# SchematicComplet.net
KiCad netlist of a schematic drawn in Altium Designer
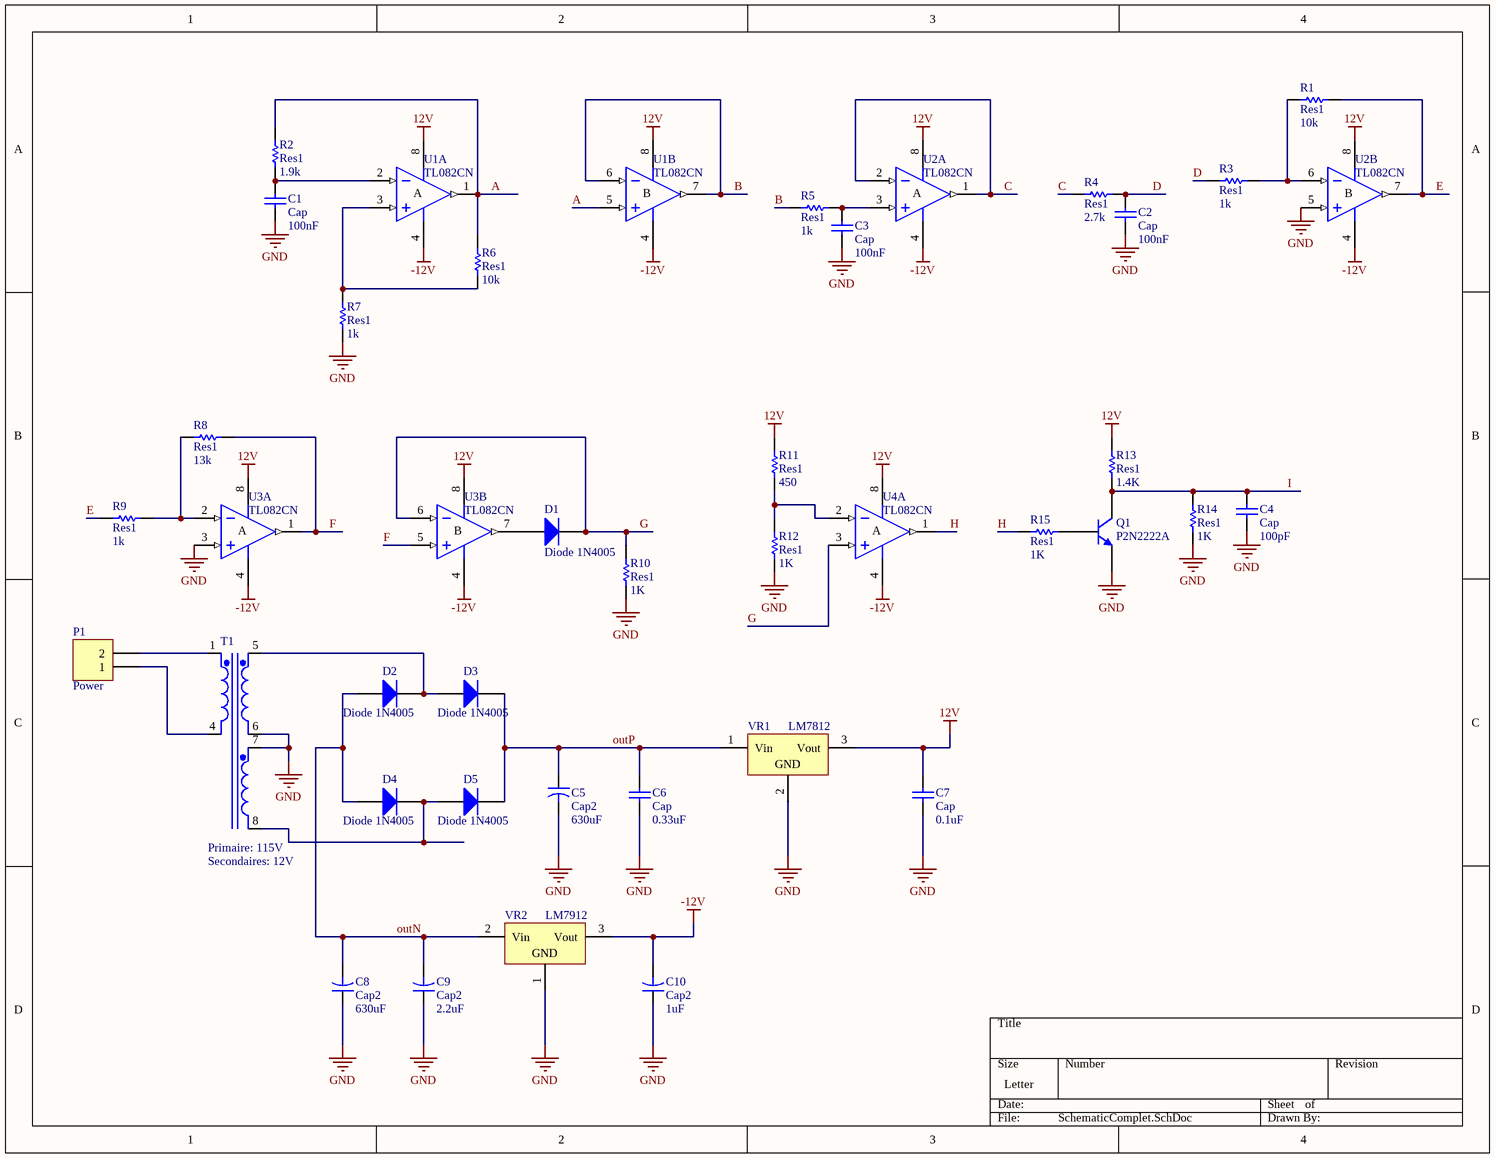
[diagram p0: SchematicComplet.SchDoc]

(export (version "E")
  (design (tool "Eeschema 10.0.6"))
  (components
    (comp (ref "C1")
      (value "Cap")
      (footprint "RAD-0.2")
      (description "Capacitor")
      (fields (field (name "ALTIUM_VALUE") "100nF") (field (name "PUBLISHER") "Altium Limited"))
      (libsource (lib "Miscellaneous Devices") (part "Cap"))
    )
    (comp (ref "C2")
      (value "Cap")
      (footprint "RAD-0.2")
      (description "Capacitor")
      (fields (field (name "ALTIUM_VALUE") "100nF") (field (name "PUBLISHER") "Altium Limited"))
      (libsource (lib "Miscellaneous Devices") (part "Cap"))
    )
    (comp (ref "C3")
      (value "Cap")
      (footprint "RAD-0.2")
      (description "Capacitor")
      (fields (field (name "ALTIUM_VALUE") "100nF") (field (name "PUBLISHER") "Altium Limited"))
      (libsource (lib "Miscellaneous Devices") (part "Cap"))
    )
    (comp (ref "C4")
      (value "Cap")
      (footprint "RAD-0.2")
      (description "Capacitor")
      (fields (field (name "ALTIUM_VALUE") "100pF") (field (name "PUBLISHER") "Altium Limited"))
      (libsource (lib "Miscellaneous Devices") (part "Cap"))
    )
    (comp (ref "C5")
      (value "Cap2")
      (footprint "Cap-10uF")
      (description "Capacitor")
      (fields (field (name "ALTIUM_VALUE") "630uF") (field (name "PUBLISHER") "Altium Limited"))
      (libsource (lib "Miscellaneous Devices") (part "Cap2"))
    )
    (comp (ref "C6")
      (value "Cap")
      (footprint "RAD-0.2")
      (description "Capacitor")
      (fields (field (name "ALTIUM_VALUE") "0.33uF") (field (name "PUBLISHER") "Altium Limited"))
      (libsource (lib "Miscellaneous Devices") (part "Cap"))
    )
    (comp (ref "C7")
      (value "Cap")
      (footprint "RAD-0.2")
      (description "Capacitor")
      (fields (field (name "ALTIUM_VALUE") "0.1uF") (field (name "PUBLISHER") "Altium Limited"))
      (libsource (lib "Miscellaneous Devices") (part "Cap"))
    )
    (comp (ref "C8")
      (value "Cap2")
      (footprint "Cap-10uF")
      (description "Capacitor")
      (fields (field (name "ALTIUM_VALUE") "630uF") (field (name "PUBLISHER") "Altium Limited"))
      (libsource (lib "Miscellaneous Devices") (part "Cap2"))
    )
    (comp (ref "C9")
      (value "Cap2")
      (footprint "Cap-10uF")
      (description "Capacitor")
      (fields (field (name "ALTIUM_VALUE") "2.2uF") (field (name "PUBLISHER") "Altium Limited"))
      (libsource (lib "Miscellaneous Devices") (part "Cap2"))
    )
    (comp (ref "C10")
      (value "Cap2")
      (footprint "Cap-10uF")
      (description "Capacitor")
      (fields (field (name "ALTIUM_VALUE") "1uF") (field (name "PUBLISHER") "Altium Limited"))
      (libsource (lib "Miscellaneous Devices") (part "Cap2"))
    )
    (comp (ref "D1")
      (value "Diode 1N4005")
      (footprint "DO-41 modifie")
      (description "1 Amp General Purpose Rectifier")
      (fields (field (name "PUBLISHER") "Altium Limited"))
      (libsource (lib "Miscellaneous Devices") (part "Diode 1N4005"))
    )
    (comp (ref "D2")
      (value "Diode 1N4005")
      (footprint "DO-41 modifie")
      (description "1 Amp General Purpose Rectifier")
      (fields (field (name "PUBLISHER") "Altium Limited"))
      (libsource (lib "Miscellaneous Devices") (part "Diode 1N4005"))
    )
    (comp (ref "D3")
      (value "Diode 1N4005")
      (footprint "DO-41 modifie")
      (description "1 Amp General Purpose Rectifier")
      (fields (field (name "PUBLISHER") "Altium Limited"))
      (libsource (lib "Miscellaneous Devices") (part "Diode 1N4005"))
    )
    (comp (ref "D4")
      (value "Diode 1N4005")
      (footprint "DO-41 modifie")
      (description "1 Amp General Purpose Rectifier")
      (fields (field (name "PUBLISHER") "Altium Limited"))
      (libsource (lib "Miscellaneous Devices") (part "Diode 1N4005"))
    )
    (comp (ref "D5")
      (value "Diode 1N4005")
      (footprint "DO-41 modifie")
      (description "1 Amp General Purpose Rectifier")
      (fields (field (name "PUBLISHER") "Altium Limited"))
      (libsource (lib "Miscellaneous Devices") (part "Diode 1N4005"))
    )
    (comp (ref "P1")
      (value "Power")
      (footprint "Bornier")
      (description "Header, 2-Pin")
      (fields (field (name "PUBLISHER") "Altium Limited"))
      (libsource (lib "Miscellaneous Connectors") (part "Header 2"))
    )
    (comp (ref "Q1")
      (value "P2N2222A")
      (footprint "29-04 modifie")
      (description "Amplifier Transistor NPN Silicon")
      (fields (field (name "PUBLISHER") "Altium Limited"))
      (libsource (lib "Motorola Discrete BJT") (part "P2N2222A"))
    )
    (comp (ref "R1")
      (value "Res1")
      (footprint "AXIAL-0.3 modifie")
      (description "Resistor")
      (fields (field (name "ALTIUM_VALUE") "10k") (field (name "PUBLISHER") "Altium Limited"))
      (libsource (lib "Miscellaneous Devices") (part "Res1"))
    )
    (comp (ref "R2")
      (value "Res1")
      (footprint "AXIAL-0.3 modifie")
      (description "Resistor")
      (fields (field (name "ALTIUM_VALUE") "1.9k") (field (name "PUBLISHER") "Altium Limited"))
      (libsource (lib "Miscellaneous Devices") (part "Res1"))
    )
    (comp (ref "R3")
      (value "Res1")
      (footprint "AXIAL-0.3 modifie")
      (description "Resistor")
      (fields (field (name "ALTIUM_VALUE") "1k") (field (name "PUBLISHER") "Altium Limited"))
      (libsource (lib "Miscellaneous Devices") (part "Res1"))
    )
    (comp (ref "R4")
      (value "Res1")
      (footprint "AXIAL-0.3 modifie")
      (description "Resistor")
      (fields (field (name "ALTIUM_VALUE") "2.7k") (field (name "PUBLISHER") "Altium Limited"))
      (libsource (lib "Miscellaneous Devices") (part "Res1"))
    )
    (comp (ref "R5")
      (value "Res1")
      (footprint "AXIAL-0.3 modifie")
      (description "Resistor")
      (fields (field (name "ALTIUM_VALUE") "1k") (field (name "PUBLISHER") "Altium Limited"))
      (libsource (lib "Miscellaneous Devices") (part "Res1"))
    )
    (comp (ref "R6")
      (value "Res1")
      (footprint "AXIAL-0.3 modifie")
      (description "Resistor")
      (fields (field (name "ALTIUM_VALUE") "10k") (field (name "PUBLISHER") "Altium Limited"))
      (libsource (lib "Miscellaneous Devices") (part "Res1"))
    )
    (comp (ref "R7")
      (value "Res1")
      (footprint "AXIAL-0.3 modifie")
      (description "Resistor")
      (fields (field (name "ALTIUM_VALUE") "1k") (field (name "PUBLISHER") "Altium Limited"))
      (libsource (lib "Miscellaneous Devices") (part "Res1"))
    )
    (comp (ref "R8")
      (value "Res1")
      (footprint "AXIAL-0.3 modifie")
      (description "Resistor")
      (fields (field (name "ALTIUM_VALUE") "13k") (field (name "PUBLISHER") "Altium Limited"))
      (libsource (lib "Miscellaneous Devices") (part "Res1"))
    )
    (comp (ref "R9")
      (value "Res1")
      (footprint "AXIAL-0.3 modifie")
      (description "Resistor")
      (fields (field (name "ALTIUM_VALUE") "1k") (field (name "PUBLISHER") "Altium Limited"))
      (libsource (lib "Miscellaneous Devices") (part "Res1"))
    )
    (comp (ref "R10")
      (value "Res1")
      (footprint "AXIAL-0.3 modifie")
      (description "Resistor")
      (fields (field (name "ALTIUM_VALUE") "1K") (field (name "PUBLISHER") "Altium Limited"))
      (libsource (lib "Miscellaneous Devices") (part "Res1"))
    )
    (comp (ref "R11")
      (value "Res1")
      (footprint "AXIAL-0.3 modifie")
      (description "Resistor")
      (fields (field (name "ALTIUM_VALUE") "450") (field (name "PUBLISHER") "Altium Limited"))
      (libsource (lib "Miscellaneous Devices") (part "Res1"))
    )
    (comp (ref "R12")
      (value "Res1")
      (footprint "AXIAL-0.3 modifie")
      (description "Resistor")
      (fields (field (name "ALTIUM_VALUE") "1K") (field (name "PUBLISHER") "Altium Limited"))
      (libsource (lib "Miscellaneous Devices") (part "Res1"))
    )
    (comp (ref "R13")
      (value "Res1")
      (footprint "AXIAL-0.3 modifie")
      (description "Resistor")
      (fields (field (name "ALTIUM_VALUE") "1.4K") (field (name "PUBLISHER") "Altium Limited"))
      (libsource (lib "Miscellaneous Devices") (part "Res1"))
    )
    (comp (ref "R14")
      (value "Res1")
      (footprint "AXIAL-0.3 modifie")
      (description "Resistor")
      (fields (field (name "ALTIUM_VALUE") "1K") (field (name "PUBLISHER") "Altium Limited"))
      (libsource (lib "Miscellaneous Devices") (part "Res1"))
    )
    (comp (ref "R15")
      (value "Res1")
      (footprint "AXIAL-0.3 modifie")
      (description "Resistor")
      (fields (field (name "ALTIUM_VALUE") "1K") (field (name "PUBLISHER") "Altium Limited"))
      (libsource (lib "Miscellaneous Devices") (part "Res1"))
    )
    (comp (ref "T1")
      (value "Trans3")
      (footprint "Transf-ST-4-24")
      (description "Three-winding Transformer (Non-Ideal)")
      (fields
        (field (name "PRIMAIRE") "115V")
        (field (name "SECONDAIRES") "12V")
        (field (name "PUBLISHER") "Altium Limited")
      )
      (libsource (lib "Miscellaneous Devices") (part "Trans3"))
    )
    (comp (ref "U1")
      (value "TL082CN")
      (footprint "TL082CN")
      (description "General-Purpose J-FET Dual Operational Amplifier")
      (fields (field (name "PUBLISHER") "Altium Limited"))
      (libsource (lib "ST Operational Amplifier") (part "TL082CN"))
    )
    (comp (ref "U2")
      (value "TL082CN")
      (footprint "TL082CN")
      (description "General-Purpose J-FET Dual Operational Amplifier")
      (fields (field (name "PUBLISHER") "Altium Limited"))
      (libsource (lib "ST Operational Amplifier") (part "TL082CN"))
    )
    (comp (ref "U3")
      (value "TL082CN")
      (footprint "TL082CN")
      (description "General-Purpose J-FET Dual Operational Amplifier")
      (fields (field (name "PUBLISHER") "Altium Limited"))
      (libsource (lib "ST Operational Amplifier") (part "TL082CN"))
    )
    (comp (ref "U4")
      (value "TL082CN")
      (footprint "TL082CN")
      (description "General-Purpose J-FET Dual Operational Amplifier")
      (fields (field (name "PUBLISHER") "Altium Limited"))
      (libsource (lib "ST Operational Amplifier") (part "TL082CN"))
    )
    (comp (ref "VR1")
      (value "LM7812")
      (footprint "TO-220-AB")
      (description "Voltage Regulator")
      (fields (field (name "PUBLISHER") "Altium Limited"))
      (libsource (lib "") (part "Volt Reg_1"))
    )
    (comp (ref "VR2")
      (value "LM7912")
      (footprint "TO-220-AB")
      (description "Voltage Regulator")
      (fields (field (name "PUBLISHER") "Altium Limited"))
      (libsource (lib "Miscellaneous Devices") (part "Volt Reg"))
    )
  )
  (nets
    (net (code "1") (name "-12V") (class "Default")
      (node (ref "C10") (pin "2") (pinfunction "2_2") (pintype "passive"))
      (node (ref "U1") (pin "4") (pinfunction "V-_4") (pintype "power_in"))
      (node (ref "U2") (pin "4") (pinfunction "V-_4") (pintype "power_in"))
      (node (ref "U3") (pin "4") (pinfunction "V-_4") (pintype "power_in"))
      (node (ref "U4") (pin "4") (pinfunction "V-_4") (pintype "power_in"))
      (node (ref "VR2") (pin "3") (pinfunction "Vout_3") (pintype "passive"))
    )
    (net (code "2") (name "/A") (class "Default")
      (node (ref "R2") (pin "2") (pinfunction "2_2") (pintype "passive"))
      (node (ref "R6") (pin "2") (pinfunction "2_2") (pintype "passive"))
      (node (ref "U1") (pin "1") (pinfunction "OUT_1") (pintype "output"))
      (node (ref "U1") (pin "5") (pinfunction "IN+_5") (pintype "input"))
    )
    (net (code "3") (name "/B") (class "Default")
      (node (ref "R5") (pin "1") (pinfunction "1_1") (pintype "passive"))
      (node (ref "U1") (pin "6") (pinfunction "IN-_6") (pintype "input"))
      (node (ref "U1") (pin "7") (pinfunction "OUT_7") (pintype "output"))
    )
    (net (code "4") (name "/C") (class "Default")
      (node (ref "R4") (pin "1") (pinfunction "1_1") (pintype "passive"))
      (node (ref "U2") (pin "1") (pinfunction "OUT_1") (pintype "output"))
      (node (ref "U2") (pin "2") (pinfunction "IN-_2") (pintype "input"))
    )
    (net (code "5") (name "/D") (class "Default")
      (node (ref "C2") (pin "2") (pinfunction "2_2") (pintype "passive"))
      (node (ref "R3") (pin "1") (pinfunction "1_1") (pintype "passive"))
      (node (ref "R4") (pin "2") (pinfunction "2_2") (pintype "passive"))
    )
    (net (code "6") (name "/E") (class "Default")
      (node (ref "R1") (pin "2") (pinfunction "2_2") (pintype "passive"))
      (node (ref "R9") (pin "1") (pinfunction "1_1") (pintype "passive"))
      (node (ref "U2") (pin "7") (pinfunction "OUT_7") (pintype "output"))
    )
    (net (code "7") (name "/F") (class "Default")
      (node (ref "R8") (pin "2") (pinfunction "2_2") (pintype "passive"))
      (node (ref "U3") (pin "1") (pinfunction "OUT_1") (pintype "output"))
      (node (ref "U3") (pin "5") (pinfunction "IN+_5") (pintype "input"))
    )
    (net (code "8") (name "/G") (class "Default")
      (node (ref "D1") (pin "2") (pinfunction "K_2") (pintype "passive"))
      (node (ref "R10") (pin "2") (pinfunction "2_2") (pintype "passive"))
      (node (ref "U3") (pin "6") (pinfunction "IN-_6") (pintype "input"))
      (node (ref "U4") (pin "3") (pinfunction "IN+_3") (pintype "input"))
    )
    (net (code "9") (name "/H") (class "Default")
      (node (ref "R15") (pin "2") (pinfunction "2_2") (pintype "passive"))
      (node (ref "U4") (pin "1") (pinfunction "OUT_1") (pintype "output"))
    )
    (net (code "10") (name "/I") (class "Default")
      (node (ref "C4") (pin "2") (pinfunction "2_2") (pintype "passive"))
      (node (ref "Q1") (pin "1") (pinfunction "C_1") (pintype "passive"))
      (node (ref "R13") (pin "1") (pinfunction "1_1") (pintype "passive"))
      (node (ref "R14") (pin "2") (pinfunction "2_2") (pintype "passive"))
    )
    (net (code "11") (name "/outN") (class "Default")
      (node (ref "C8") (pin "2") (pinfunction "2_2") (pintype "passive"))
      (node (ref "C9") (pin "2") (pinfunction "2_2") (pintype "passive"))
      (node (ref "D2") (pin "1") (pinfunction "A_1") (pintype "passive"))
      (node (ref "D4") (pin "1") (pinfunction "A_1") (pintype "passive"))
      (node (ref "VR2") (pin "2") (pinfunction "Vin_2") (pintype "passive"))
    )
    (net (code "12") (name "/outP") (class "Default")
      (node (ref "C5") (pin "1") (pinfunction "1_1") (pintype "passive"))
      (node (ref "C6") (pin "2") (pinfunction "2_2") (pintype "passive"))
      (node (ref "D3") (pin "2") (pinfunction "K_2") (pintype "passive"))
      (node (ref "D5") (pin "2") (pinfunction "K_2") (pintype "passive"))
      (node (ref "VR1") (pin "1") (pinfunction "Vin_1") (pintype "passive"))
    )
    (net (code "13") (name "12V") (class "Default")
      (node (ref "C7") (pin "2") (pinfunction "2_2") (pintype "passive"))
      (node (ref "R11") (pin "2") (pinfunction "2_2") (pintype "passive"))
      (node (ref "R13") (pin "2") (pinfunction "2_2") (pintype "passive"))
      (node (ref "U1") (pin "8") (pinfunction "V+_8") (pintype "power_in"))
      (node (ref "U2") (pin "8") (pinfunction "V+_8") (pintype "power_in"))
      (node (ref "U3") (pin "8") (pinfunction "V+_8") (pintype "power_in"))
      (node (ref "U4") (pin "8") (pinfunction "V+_8") (pintype "power_in"))
      (node (ref "VR1") (pin "3") (pinfunction "Vout_3") (pintype "passive"))
    )
    (net (code "14") (name "GND") (class "Default")
      (node (ref "C1") (pin "1") (pinfunction "1_1") (pintype "passive"))
      (node (ref "C10") (pin "1") (pinfunction "1_1") (pintype "passive"))
      (node (ref "C2") (pin "1") (pinfunction "1_1") (pintype "passive"))
      (node (ref "C3") (pin "1") (pinfunction "1_1") (pintype "passive"))
      (node (ref "C4") (pin "1") (pinfunction "1_1") (pintype "passive"))
      (node (ref "C5") (pin "2") (pinfunction "2_2") (pintype "passive"))
      (node (ref "C6") (pin "1") (pinfunction "1_1") (pintype "passive"))
      (node (ref "C7") (pin "1") (pinfunction "1_1") (pintype "passive"))
      (node (ref "C8") (pin "1") (pinfunction "1_1") (pintype "passive"))
      (node (ref "C9") (pin "1") (pinfunction "1_1") (pintype "passive"))
      (node (ref "Q1") (pin "3") (pinfunction "E_3") (pintype "passive"))
      (node (ref "R10") (pin "1") (pinfunction "1_1") (pintype "passive"))
      (node (ref "R12") (pin "1") (pinfunction "1_1") (pintype "passive"))
      (node (ref "R14") (pin "1") (pinfunction "1_1") (pintype "passive"))
      (node (ref "R7") (pin "1") (pinfunction "1_1") (pintype "passive"))
      (node (ref "T1") (pin "6") (pinfunction "Sec1-_6") (pintype "passive"))
      (node (ref "T1") (pin "7") (pinfunction "Sec2+_7") (pintype "passive"))
      (node (ref "U2") (pin "5") (pinfunction "IN+_5") (pintype "input"))
      (node (ref "U3") (pin "3") (pinfunction "IN+_3") (pintype "input"))
      (node (ref "VR1") (pin "2") (pinfunction "GND_2") (pintype "passive"))
      (node (ref "VR2") (pin "1") (pinfunction "GND_1") (pintype "passive"))
    )
    (net (code "15") (name "Net-(D1-A)") (class "Default")
      (node (ref "D1") (pin "1") (pinfunction "A_1") (pintype "passive"))
      (node (ref "U3") (pin "7") (pinfunction "OUT_7") (pintype "output"))
    )
    (net (code "16") (name "Net-(D2-K)") (class "Default")
      (node (ref "D2") (pin "2") (pinfunction "K_2") (pintype "passive"))
      (node (ref "D3") (pin "1") (pinfunction "A_1") (pintype "passive"))
      (node (ref "T1") (pin "5") (pinfunction "Sec1+_5") (pintype "passive"))
    )
    (net (code "17") (name "Net-(D4-K)") (class "Default")
      (node (ref "D4") (pin "2") (pinfunction "K_2") (pintype "passive"))
      (node (ref "D5") (pin "1") (pinfunction "A_1") (pintype "passive"))
      (node (ref "T1") (pin "8") (pinfunction "Sec2-_8") (pintype "passive"))
    )
    (net (code "18") (name "Net-(Q1-B)") (class "Default")
      (node (ref "Q1") (pin "2") (pinfunction "B_2") (pintype "passive"))
      (node (ref "R15") (pin "1") (pinfunction "1_1") (pintype "passive"))
    )
    (net (code "19") (name "Net-(T1-Pri+)") (class "Default")
      (node (ref "P1") (pin "2") (pinfunction "2_2") (pintype "passive"))
      (node (ref "T1") (pin "1") (pinfunction "Pri+_1") (pintype "passive"))
    )
    (net (code "20") (name "Net-(T1-Pri-)") (class "Default")
      (node (ref "P1") (pin "1") (pinfunction "1_1") (pintype "passive"))
      (node (ref "T1") (pin "4") (pinfunction "Pri-_4") (pintype "passive"))
    )
    (net (code "21") (name "Net-(U1A-IN+)") (class "Default")
      (node (ref "R6") (pin "1") (pinfunction "1_1") (pintype "passive"))
      (node (ref "R7") (pin "2") (pinfunction "2_2") (pintype "passive"))
      (node (ref "U1") (pin "3") (pinfunction "IN+_3") (pintype "input"))
    )
    (net (code "22") (name "Net-(U1A-IN-)") (class "Default")
      (node (ref "C1") (pin "2") (pinfunction "2_2") (pintype "passive"))
      (node (ref "R2") (pin "1") (pinfunction "1_1") (pintype "passive"))
      (node (ref "U1") (pin "2") (pinfunction "IN-_2") (pintype "input"))
    )
    (net (code "23") (name "Net-(U2A-IN+)") (class "Default")
      (node (ref "C3") (pin "2") (pinfunction "2_2") (pintype "passive"))
      (node (ref "R5") (pin "2") (pinfunction "2_2") (pintype "passive"))
      (node (ref "U2") (pin "3") (pinfunction "IN+_3") (pintype "input"))
    )
    (net (code "24") (name "Net-(U2B-IN-)") (class "Default")
      (node (ref "R1") (pin "1") (pinfunction "1_1") (pintype "passive"))
      (node (ref "R3") (pin "2") (pinfunction "2_2") (pintype "passive"))
      (node (ref "U2") (pin "6") (pinfunction "IN-_6") (pintype "input"))
    )
    (net (code "25") (name "Net-(U3A-IN-)") (class "Default")
      (node (ref "R8") (pin "1") (pinfunction "1_1") (pintype "passive"))
      (node (ref "R9") (pin "2") (pinfunction "2_2") (pintype "passive"))
      (node (ref "U3") (pin "2") (pinfunction "IN-_2") (pintype "input"))
    )
    (net (code "26") (name "Net-(U4A-IN-)") (class "Default")
      (node (ref "R11") (pin "1") (pinfunction "1_1") (pintype "passive"))
      (node (ref "R12") (pin "2") (pinfunction "2_2") (pintype "passive"))
      (node (ref "U4") (pin "2") (pinfunction "IN-_2") (pintype "input"))
    )
  )
)
